# Driver.net
KiCad netlist of a schematic drawn in Altium Designer
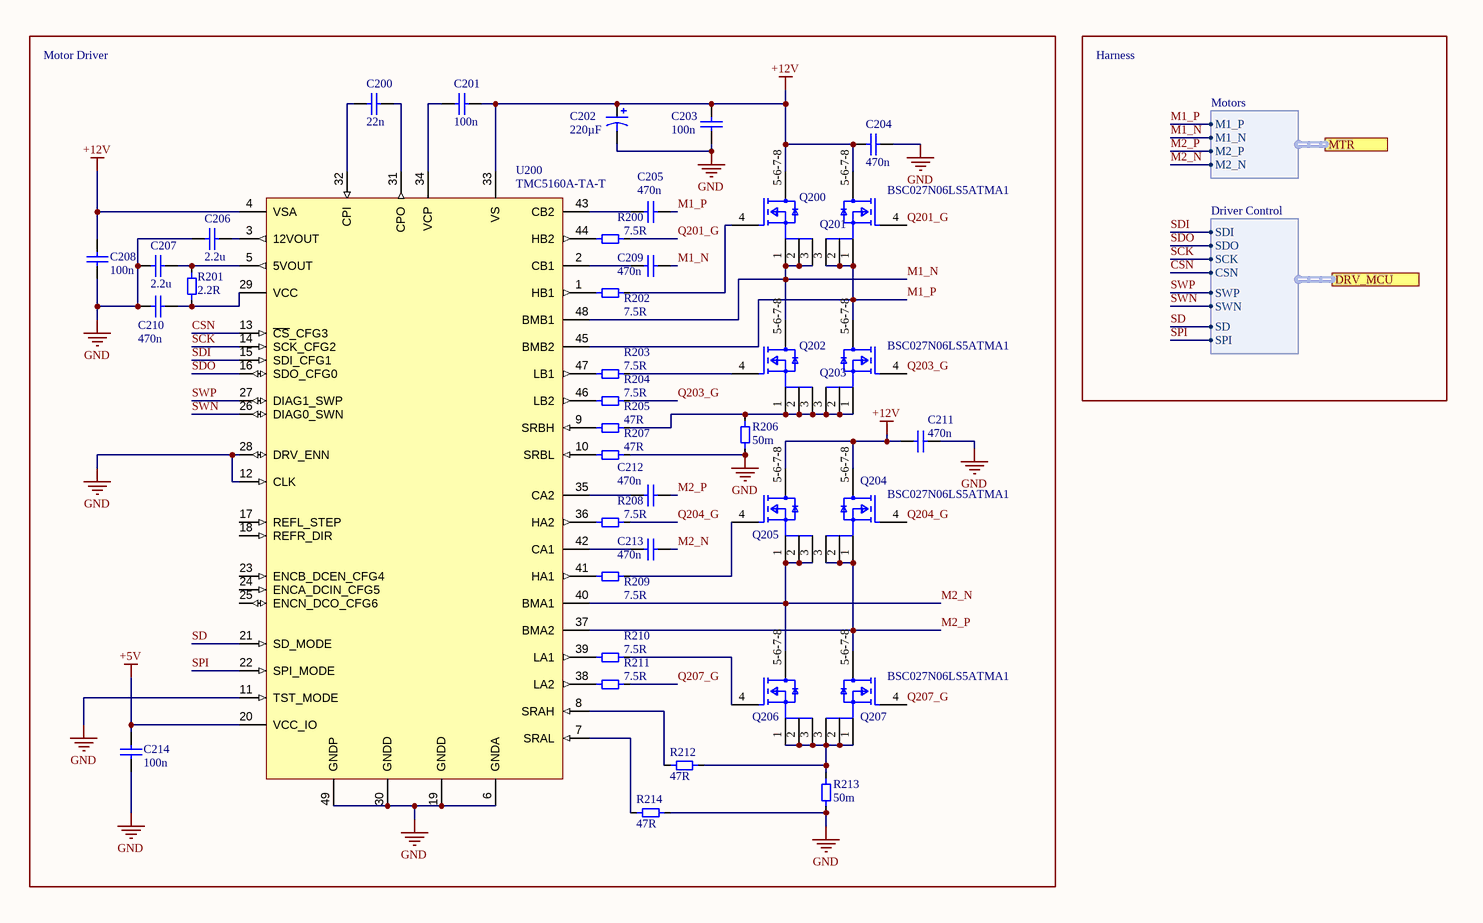
[diagram p0: Driver.SchDoc, right]

(export (version "E")
  (design (tool "Eeschema 10.0.6"))
  (components
    (comp (ref "C200")
      (value "22n")
      (footprint "MLCC_0603_M")
      (description "MLCC, 0603, 22n, 10%, 6.3V, X7R")
      (fields (field (name "MANUFACTURER") "Any") (field (name "TOLERANCE") "10%"))
      (libsource (lib "Krakul Vault") (part "CAPACITOR_NONPOL_IEC"))
    )
    (comp (ref "C201")
      (value "100n")
      (footprint "MLCC_0603_M")
      (description "MLCC, 0603, 100n, 10%, 35V, X7R")
      (fields (field (name "MANUFACTURER") "Any") (field (name "VOLTAGE") "35V"))
      (libsource (lib "Krakul Vault") (part "CAPACITOR_NONPOL_IEC"))
    )
    (comp (ref "C202")
      (value "220µF")
      (footprint "8mm Cap")
      (description "Panasonic EEUFS1H221L - Aluminum Electrolytic Capacitors (Radial Lead Type)")
      (fields (field (name "VOLTAGE") "50V") (field (name "MANUFACTURER") "Any"))
      (libsource (lib "Krakul Vault") (part "GENERIC ELECTROLYTIC CAP"))
    )
    (comp (ref "C203")
      (value "100n")
      (footprint "MLCC_0603_M")
      (description "MLCC, 0603, 100n, 10%, 35V, X7R")
      (fields (field (name "MANUFACTURER") "Any") (field (name "VOLTAGE") "35V"))
      (libsource (lib "Krakul Vault") (part "CAPACITOR_NONPOL_IEC"))
    )
    (comp (ref "C204")
      (value "470n")
      (footprint "MLCC_0805_M")
      (description "MLCC, 0805, 470n, 10%, 6.3V, X7R")
      (fields (field (name "TOLERANCE") "10%") (field (name "VOLTAGE") "6,3V"))
      (libsource (lib "Krakul Vault") (part "CAPACITOR_NONPOL_IEC"))
    )
    (comp (ref "C205")
      (value "470n")
      (footprint "MLCC_0805_M")
      (description "MLCC, 0805, 470n, 10%, 6.3V, X7R")
      (fields (field (name "TOLERANCE") "10%") (field (name "VOLTAGE") "6,3V"))
      (libsource (lib "Krakul Vault") (part "CAPACITOR_NONPOL_IEC"))
    )
    (comp (ref "C206")
      (value "2.2u")
      (footprint "MLCC_0805_M")
      (description "MLCC, 0805, 2.2u, 10%, 6.3V, X7R")
      (fields (field (name "VOLTAGE") "6,3V") (field (name "TOLERANCE") "10%"))
      (libsource (lib "Krakul Vault") (part "CAPACITOR_NONPOL_IEC"))
    )
    (comp (ref "C207")
      (value "2.2u")
      (footprint "MLCC_0805_M")
      (description "MLCC, 0805, 2.2u, 10%, 6.3V, X7R")
      (fields (field (name "VOLTAGE") "6,3V") (field (name "TOLERANCE") "10%"))
      (libsource (lib "Krakul Vault") (part "CAPACITOR_NONPOL_IEC"))
    )
    (comp (ref "C208")
      (value "100n")
      (footprint "MLCC_0603_M")
      (description "MLCC, 0603, 100n, 10%, 35V, X7R")
      (fields (field (name "MANUFACTURER") "Any") (field (name "VOLTAGE") "35V"))
      (libsource (lib "Krakul Vault") (part "CAPACITOR_NONPOL_IEC"))
    )
    (comp (ref "C209")
      (value "470n")
      (footprint "MLCC_0805_M")
      (description "MLCC, 0805, 470n, 10%, 6.3V, X7R")
      (fields (field (name "TOLERANCE") "10%") (field (name "VOLTAGE") "6,3V"))
      (libsource (lib "Krakul Vault") (part "CAPACITOR_NONPOL_IEC"))
    )
    (comp (ref "C210")
      (value "470n")
      (footprint "MLCC_0805_M")
      (description "MLCC, 0805, 470n, 10%, 6.3V, X7R")
      (fields (field (name "TOLERANCE") "10%") (field (name "VOLTAGE") "6,3V"))
      (libsource (lib "Krakul Vault") (part "CAPACITOR_NONPOL_IEC"))
    )
    (comp (ref "C211")
      (value "470n")
      (footprint "MLCC_0805_M")
      (description "MLCC, 0805, 470n, 10%, 6.3V, X7R")
      (fields (field (name "TOLERANCE") "10%") (field (name "VOLTAGE") "6,3V"))
      (libsource (lib "Krakul Vault") (part "CAPACITOR_NONPOL_IEC"))
    )
    (comp (ref "C212")
      (value "470n")
      (footprint "MLCC_0805_M")
      (description "MLCC, 0805, 470n, 10%, 6.3V, X7R")
      (fields (field (name "TOLERANCE") "10%") (field (name "VOLTAGE") "6,3V"))
      (libsource (lib "Krakul Vault") (part "CAPACITOR_NONPOL_IEC"))
    )
    (comp (ref "C213")
      (value "470n")
      (footprint "MLCC_0805_M")
      (description "MLCC, 0805, 470n, 10%, 6.3V, X7R")
      (fields (field (name "TOLERANCE") "10%") (field (name "VOLTAGE") "6,3V"))
      (libsource (lib "Krakul Vault") (part "CAPACITOR_NONPOL_IEC"))
    )
    (comp (ref "C214")
      (value "100n")
      (footprint "MLCC_0603_M")
      (description "MLCC, 0603, 100n, 10%, 35V, X7R")
      (fields (field (name "MANUFACTURER") "Any") (field (name "VOLTAGE") "35V"))
      (libsource (lib "Krakul Vault") (part "CAPACITOR_NONPOL_IEC"))
    )
    (comp (ref "Q200")
      (value "BSC027N06LS5ATMA1")
      (footprint "FP-PG-TDSON-8-MFG")
      (description "Power MOSFET, N Channel, 60 V, 100 A, 0.0027 ohm, TDSON, Surface Mount")
      (fields (field (name "MANUFACTURER") "Infineon Technologies"))
      (libsource (lib "Krakul Vault") (part "d156af113c66deab26b3d7f562d4ecf"))
    )
    (comp (ref "Q201")
      (value "BSC027N06LS5ATMA1")
      (footprint "FP-PG-TDSON-8-MFG")
      (description "Power MOSFET, N Channel, 60 V, 100 A, 0.0027 ohm, TDSON, Surface Mount")
      (fields (field (name "MANUFACTURER") "Infineon Technologies"))
      (libsource (lib "Krakul Vault") (part "d156af113c66deab26b3d7f562d4ecf"))
    )
    (comp (ref "Q202")
      (value "BSC027N06LS5ATMA1")
      (footprint "FP-PG-TDSON-8-MFG")
      (description "Power MOSFET, N Channel, 60 V, 100 A, 0.0027 ohm, TDSON, Surface Mount")
      (fields (field (name "MANUFACTURER") "Infineon Technologies"))
      (libsource (lib "Krakul Vault") (part "d156af113c66deab26b3d7f562d4ecf"))
    )
    (comp (ref "Q203")
      (value "BSC027N06LS5ATMA1")
      (footprint "FP-PG-TDSON-8-MFG")
      (description "Power MOSFET, N Channel, 60 V, 100 A, 0.0027 ohm, TDSON, Surface Mount")
      (fields (field (name "MANUFACTURER") "Infineon Technologies"))
      (libsource (lib "Krakul Vault") (part "d156af113c66deab26b3d7f562d4ecf"))
    )
    (comp (ref "Q204")
      (value "BSC027N06LS5ATMA1")
      (footprint "FP-PG-TDSON-8-MFG")
      (description "Power MOSFET, N Channel, 60 V, 100 A, 0.0027 ohm, TDSON, Surface Mount")
      (fields (field (name "MANUFACTURER") "Infineon Technologies"))
      (libsource (lib "Krakul Vault") (part "d156af113c66deab26b3d7f562d4ecf"))
    )
    (comp (ref "Q205")
      (value "BSC027N06LS5ATMA1")
      (footprint "FP-PG-TDSON-8-MFG")
      (description "Power MOSFET, N Channel, 60 V, 100 A, 0.0027 ohm, TDSON, Surface Mount")
      (fields (field (name "MANUFACTURER") "Infineon Technologies"))
      (libsource (lib "Krakul Vault") (part "d156af113c66deab26b3d7f562d4ecf"))
    )
    (comp (ref "Q206")
      (value "BSC027N06LS5ATMA1")
      (footprint "FP-PG-TDSON-8-MFG")
      (description "Power MOSFET, N Channel, 60 V, 100 A, 0.0027 ohm, TDSON, Surface Mount")
      (fields (field (name "MANUFACTURER") "Infineon Technologies"))
      (libsource (lib "Krakul Vault") (part "d156af113c66deab26b3d7f562d4ecf"))
    )
    (comp (ref "Q207")
      (value "BSC027N06LS5ATMA1")
      (footprint "FP-PG-TDSON-8-MFG")
      (description "Power MOSFET, N Channel, 60 V, 100 A, 0.0027 ohm, TDSON, Surface Mount")
      (fields (field (name "MANUFACTURER") "Infineon Technologies"))
      (libsource (lib "Krakul Vault") (part "d156af113c66deab26b3d7f562d4ecf"))
    )
    (comp (ref "R200")
      (value "7.5R")
      (footprint "Resistor_0603_M")
      (description "Resistor, 0603, 7.5R, 1%, 1/10W")
      (fields (field (name "POWER") "100mW") (field (name "TOLERANCE") "1%"))
      (libsource (lib "Krakul Vault") (part "RESISTOR_GENERIC_IEC"))
    )
    (comp (ref "R201")
      (value "2.2R")
      (footprint "Resistor_0603_M")
      (description "Resistor, 0603, 2.2R, 1%, 1/10W")
      (fields (field (name "MANUFACTURER") "Any") (field (name "POWER") "100mW"))
      (libsource (lib "Krakul Vault") (part "RESISTOR_GENERIC_IEC"))
    )
    (comp (ref "R202")
      (value "7.5R")
      (footprint "Resistor_0603_M")
      (description "Resistor, 0603, 7.5R, 1%, 1/10W")
      (fields (field (name "POWER") "100mW") (field (name "TOLERANCE") "1%"))
      (libsource (lib "Krakul Vault") (part "RESISTOR_GENERIC_IEC"))
    )
    (comp (ref "R203")
      (value "7.5R")
      (footprint "Resistor_0603_M")
      (description "Resistor, 0603, 7.5R, 1%, 1/10W")
      (fields (field (name "POWER") "100mW") (field (name "TOLERANCE") "1%"))
      (libsource (lib "Krakul Vault") (part "RESISTOR_GENERIC_IEC"))
    )
    (comp (ref "R204")
      (value "7.5R")
      (footprint "Resistor_0603_M")
      (description "Resistor, 0603, 7.5R, 1%, 1/10W")
      (fields (field (name "POWER") "100mW") (field (name "TOLERANCE") "1%"))
      (libsource (lib "Krakul Vault") (part "RESISTOR_GENERIC_IEC"))
    )
    (comp (ref "R205")
      (value "47R")
      (footprint "Resistor_0603_M")
      (description "Resistor, 0603, 47R, 1%, 1/10W")
      (fields (field (name "TOLERANCE") "1%") (field (name "MANUFACTURER") "Any"))
      (libsource (lib "Krakul Vault") (part "RESISTOR_GENERIC_IEC"))
    )
    (comp (ref "R206")
      (value "50m")
      (footprint "PE0612FKM7W0R05L-Footprint-1")
      (description "Current Sensor-Low TCR Chip Resistor Wide Terminal Metal Alloy 0612 50mOhm 1% Emboss T/R")
      (fields (field (name "MANUFACTURER") "Any") (field (name "PART NUMBER") "PE0612FKM7W0R05L"))
      (libsource (lib "Krakul Vault") (part "RESISTOR_WITH_SENSE"))
    )
    (comp (ref "R207")
      (value "47R")
      (footprint "Resistor_0603_M")
      (description "Resistor, 0603, 47R, 1%, 1/10W")
      (fields (field (name "TOLERANCE") "1%") (field (name "MANUFACTURER") "Any"))
      (libsource (lib "Krakul Vault") (part "RESISTOR_GENERIC_IEC"))
    )
    (comp (ref "R208")
      (value "7.5R")
      (footprint "Resistor_0603_M")
      (description "Resistor, 0603, 7.5R, 1%, 1/10W")
      (fields (field (name "POWER") "100mW") (field (name "TOLERANCE") "1%"))
      (libsource (lib "Krakul Vault") (part "RESISTOR_GENERIC_IEC"))
    )
    (comp (ref "R209")
      (value "7.5R")
      (footprint "Resistor_0603_M")
      (description "Resistor, 0603, 7.5R, 1%, 1/10W")
      (fields (field (name "POWER") "100mW") (field (name "TOLERANCE") "1%"))
      (libsource (lib "Krakul Vault") (part "RESISTOR_GENERIC_IEC"))
    )
    (comp (ref "R210")
      (value "7.5R")
      (footprint "Resistor_0603_M")
      (description "Resistor, 0603, 7.5R, 1%, 1/10W")
      (fields (field (name "POWER") "100mW") (field (name "TOLERANCE") "1%"))
      (libsource (lib "Krakul Vault") (part "RESISTOR_GENERIC_IEC"))
    )
    (comp (ref "R211")
      (value "7.5R")
      (footprint "Resistor_0603_M")
      (description "Resistor, 0603, 7.5R, 1%, 1/10W")
      (fields (field (name "POWER") "100mW") (field (name "TOLERANCE") "1%"))
      (libsource (lib "Krakul Vault") (part "RESISTOR_GENERIC_IEC"))
    )
    (comp (ref "R212")
      (value "47R")
      (footprint "Resistor_0603_M")
      (description "Resistor, 0603, 47R, 1%, 1/10W")
      (fields (field (name "TOLERANCE") "1%") (field (name "MANUFACTURER") "Any"))
      (libsource (lib "Krakul Vault") (part "RESISTOR_GENERIC_IEC"))
    )
    (comp (ref "R213")
      (value "50m")
      (footprint "PE0612FKM7W0R05L-Footprint-1")
      (description "Current Sensor-Low TCR Chip Resistor Wide Terminal Metal Alloy 0612 50mOhm 1% Emboss T/R")
      (fields (field (name "MANUFACTURER") "Any") (field (name "PART NUMBER") "PE0612FKM7W0R05L"))
      (libsource (lib "Krakul Vault") (part "RESISTOR_WITH_SENSE"))
    )
    (comp (ref "R214")
      (value "47R")
      (footprint "Resistor_0603_M")
      (description "Resistor, 0603, 47R, 1%, 1/10W")
      (fields (field (name "TOLERANCE") "1%") (field (name "MANUFACTURER") "Any"))
      (libsource (lib "Krakul Vault") (part "RESISTOR_GENERIC_IEC"))
    )
    (comp (ref "U200")
      (value "TMC5160A-TA-T")
      (footprint "TQFP80P900X900X120-32N")
      (description "IC Mtr Drvr Bipolar 8-60V 48TQFP")
      (fields (field (name "MANUFACTURER") "Trinamic Motion Control GmbH"))
      (libsource (lib "Krakul Vault") (part "TMC5160A-TA"))
    )
  )
  (nets
    (net (code "4") (name "+5V") (class "Default")
      (node (ref "C214") (pin "2") (pinfunction "2_2") (pintype "passive"))
      (node (ref "U200") (pin "20") (pinfunction "VCC_IO_20") (pintype "power_in"))
    )
    (net (code "5") (name "+12V") (class "Default")
      (node (ref "C201") (pin "1") (pinfunction "1_1") (pintype "passive"))
      (node (ref "C202") (pin "2") (pinfunction "2_2") (pintype "passive"))
      (node (ref "C203") (pin "2") (pinfunction "2_2") (pintype "passive"))
      (node (ref "C204") (pin "2") (pinfunction "2_2") (pintype "passive"))
      (node (ref "C208") (pin "2") (pinfunction "2_2") (pintype "passive"))
      (node (ref "C211") (pin "1") (pinfunction "1_1") (pintype "passive"))
      (node (ref "Q200") (pin "5-6-7-8") (pinfunction "D_5-6-7-8") (pintype "passive"))
      (node (ref "Q201") (pin "5-6-7-8") (pinfunction "D_5-6-7-8") (pintype "passive"))
      (node (ref "Q204") (pin "5-6-7-8") (pinfunction "D_5-6-7-8") (pintype "passive"))
      (node (ref "Q205") (pin "5-6-7-8") (pinfunction "D_5-6-7-8") (pintype "passive"))
      (node (ref "U200") (pin "33") (pinfunction "VS_33") (pintype "power_in"))
      (node (ref "U200") (pin "4") (pinfunction "VSA_4") (pintype "power_in"))
    )
    (net (code "6") (name "/CSN") (class "Default")
      (node (ref "U200") (pin "13") (pinfunction "~{CS}_CFG3_13") (pintype "input"))
    )
    (net (code "7") (name "/M1_N") (class "Default")
      (node (ref "C209") (pin "2") (pinfunction "2_2") (pintype "passive"))
      (node (ref "Q200") (pin "1") (pinfunction "S_1") (pintype "passive"))
      (node (ref "Q200") (pin "2") (pinfunction "S_2") (pintype "passive"))
      (node (ref "Q200") (pin "3") (pinfunction "S_3") (pintype "passive"))
      (node (ref "Q202") (pin "5-6-7-8") (pinfunction "D_5-6-7-8") (pintype "passive"))
      (node (ref "U200") (pin "48") (pinfunction "BMB1_48") (pintype "passive"))
    )
    (net (code "8") (name "/M1_P") (class "Default")
      (node (ref "C205") (pin "2") (pinfunction "2_2") (pintype "passive"))
      (node (ref "Q201") (pin "1") (pinfunction "S_1") (pintype "passive"))
      (node (ref "Q201") (pin "2") (pinfunction "S_2") (pintype "passive"))
      (node (ref "Q201") (pin "3") (pinfunction "S_3") (pintype "passive"))
      (node (ref "Q203") (pin "5-6-7-8") (pinfunction "D_5-6-7-8") (pintype "passive"))
      (node (ref "U200") (pin "45") (pinfunction "BMB2_45") (pintype "passive"))
    )
    (net (code "9") (name "/M2_N") (class "Default")
      (node (ref "C213") (pin "2") (pinfunction "2_2") (pintype "passive"))
      (node (ref "Q205") (pin "1") (pinfunction "S_1") (pintype "passive"))
      (node (ref "Q205") (pin "2") (pinfunction "S_2") (pintype "passive"))
      (node (ref "Q205") (pin "3") (pinfunction "S_3") (pintype "passive"))
      (node (ref "Q206") (pin "5-6-7-8") (pinfunction "D_5-6-7-8") (pintype "passive"))
      (node (ref "U200") (pin "40") (pinfunction "BMA1_40") (pintype "passive"))
    )
    (net (code "10") (name "/M2_P") (class "Default")
      (node (ref "C212") (pin "2") (pinfunction "2_2") (pintype "passive"))
      (node (ref "Q204") (pin "1") (pinfunction "S_1") (pintype "passive"))
      (node (ref "Q204") (pin "2") (pinfunction "S_2") (pintype "passive"))
      (node (ref "Q204") (pin "3") (pinfunction "S_3") (pintype "passive"))
      (node (ref "Q207") (pin "5-6-7-8") (pinfunction "D_5-6-7-8") (pintype "passive"))
      (node (ref "U200") (pin "37") (pinfunction "BMA2_37") (pintype "passive"))
    )
    (net (code "11") (name "/Q201_G") (class "Default")
      (node (ref "Q201") (pin "4") (pinfunction "G_4") (pintype "passive"))
      (node (ref "R200") (pin "2") (pinfunction "2_2") (pintype "passive"))
    )
    (net (code "12") (name "/Q203_G") (class "Default")
      (node (ref "Q203") (pin "4") (pinfunction "G_4") (pintype "passive"))
      (node (ref "R204") (pin "2") (pinfunction "2_2") (pintype "passive"))
    )
    (net (code "13") (name "/Q204_G") (class "Default")
      (node (ref "Q204") (pin "4") (pinfunction "G_4") (pintype "passive"))
      (node (ref "R208") (pin "2") (pinfunction "2_2") (pintype "passive"))
    )
    (net (code "14") (name "/Q207_G") (class "Default")
      (node (ref "Q207") (pin "4") (pinfunction "G_4") (pintype "passive"))
      (node (ref "R211") (pin "2") (pinfunction "2_2") (pintype "passive"))
    )
    (net (code "15") (name "/SCK") (class "Default")
      (node (ref "U200") (pin "14") (pinfunction "SCK_CFG2_14") (pintype "input"))
    )
    (net (code "16") (name "/SD") (class "Default")
      (node (ref "U200") (pin "21") (pinfunction "SD_MODE_21") (pintype "input"))
    )
    (net (code "17") (name "/SDI") (class "Default")
      (node (ref "U200") (pin "15") (pinfunction "SDI_CFG1_15") (pintype "input"))
    )
    (net (code "18") (name "/SDO") (class "Default")
      (node (ref "U200") (pin "16") (pinfunction "SDO_CFG0_16") (pintype "bidirectional"))
    )
    (net (code "19") (name "/SPI") (class "Default")
      (node (ref "U200") (pin "22") (pinfunction "SPI_MODE_22") (pintype "input"))
    )
    (net (code "20") (name "/SWN") (class "Default")
      (node (ref "U200") (pin "26") (pinfunction "DIAG0_SWN_26") (pintype "bidirectional"))
    )
    (net (code "21") (name "/SWP") (class "Default")
      (node (ref "U200") (pin "27") (pinfunction "DIAG1_SWP_27") (pintype "bidirectional"))
    )
    (net (code "24") (name "GND") (class "Default")
      (node (ref "C202") (pin "1") (pinfunction "1_1") (pintype "passive"))
      (node (ref "C203") (pin "1") (pinfunction "1_1") (pintype "passive"))
      (node (ref "C204") (pin "1") (pinfunction "1_1") (pintype "passive"))
      (node (ref "C206") (pin "1") (pinfunction "1_1") (pintype "passive"))
      (node (ref "C207") (pin "1") (pinfunction "1_1") (pintype "passive"))
      (node (ref "C208") (pin "1") (pinfunction "1_1") (pintype "passive"))
      (node (ref "C210") (pin "1") (pinfunction "1_1") (pintype "passive"))
      (node (ref "C211") (pin "2") (pinfunction "2_2") (pintype "passive"))
      (node (ref "C214") (pin "1") (pinfunction "1_1") (pintype "passive"))
      (node (ref "R206") (pin "1") (pinfunction "1_1") (pintype "passive"))
      (node (ref "R207") (pin "1") (pinfunction "1_1") (pintype "passive"))
      (node (ref "R213") (pin "1") (pinfunction "1_1") (pintype "passive"))
      (node (ref "R214") (pin "1") (pinfunction "1_1") (pintype "passive"))
      (node (ref "U200") (pin "11") (pinfunction "TST_MODE_11") (pintype "input"))
      (node (ref "U200") (pin "12") (pinfunction "CLK_12") (pintype "input"))
      (node (ref "U200") (pin "19") (pinfunction "GNDD_19") (pintype "power_in"))
      (node (ref "U200") (pin "28") (pinfunction "DRV_ENN_28") (pintype "bidirectional"))
      (node (ref "U200") (pin "30") (pinfunction "GNDD_30") (pintype "power_in"))
      (node (ref "U200") (pin "49") (pinfunction "GNDP_49") (pintype "power_in"))
      (node (ref "U200") (pin "6") (pinfunction "GNDA_6") (pintype "power_in"))
    )
    (net (code "25") (name "Net-(Q200-G)") (class "Default")
      (node (ref "Q200") (pin "4") (pinfunction "G_4") (pintype "passive"))
      (node (ref "R202") (pin "2") (pinfunction "2_2") (pintype "passive"))
    )
    (net (code "26") (name "Net-(Q202-G)") (class "Default")
      (node (ref "Q202") (pin "4") (pinfunction "G_4") (pintype "passive"))
      (node (ref "R203") (pin "2") (pinfunction "2_2") (pintype "passive"))
    )
    (net (code "27") (name "Net-(Q202-S-Pad1)") (class "Default")
      (node (ref "Q202") (pin "1") (pinfunction "S_1") (pintype "passive"))
      (node (ref "Q202") (pin "2") (pinfunction "S_2") (pintype "passive"))
      (node (ref "Q202") (pin "3") (pinfunction "S_3") (pintype "passive"))
      (node (ref "Q203") (pin "1") (pinfunction "S_1") (pintype "passive"))
      (node (ref "Q203") (pin "2") (pinfunction "S_2") (pintype "passive"))
      (node (ref "Q203") (pin "3") (pinfunction "S_3") (pintype "passive"))
      (node (ref "R205") (pin "1") (pinfunction "1_1") (pintype "passive"))
      (node (ref "R206") (pin "2") (pinfunction "1_2") (pintype "passive"))
    )
    (net (code "28") (name "Net-(Q205-G)") (class "Default")
      (node (ref "Q205") (pin "4") (pinfunction "G_4") (pintype "passive"))
      (node (ref "R209") (pin "2") (pinfunction "2_2") (pintype "passive"))
    )
    (net (code "29") (name "Net-(Q206-G)") (class "Default")
      (node (ref "Q206") (pin "4") (pinfunction "G_4") (pintype "passive"))
      (node (ref "R210") (pin "2") (pinfunction "2_2") (pintype "passive"))
    )
    (net (code "30") (name "Net-(Q206-S-Pad1)") (class "Default")
      (node (ref "Q206") (pin "1") (pinfunction "S_1") (pintype "passive"))
      (node (ref "Q206") (pin "2") (pinfunction "S_2") (pintype "passive"))
      (node (ref "Q206") (pin "3") (pinfunction "S_3") (pintype "passive"))
      (node (ref "Q207") (pin "1") (pinfunction "S_1") (pintype "passive"))
      (node (ref "Q207") (pin "2") (pinfunction "S_2") (pintype "passive"))
      (node (ref "Q207") (pin "3") (pinfunction "S_3") (pintype "passive"))
      (node (ref "R212") (pin "1") (pinfunction "1_1") (pintype "passive"))
      (node (ref "R213") (pin "2") (pinfunction "1_2") (pintype "passive"))
    )
    (net (code "31") (name "Net-(U200-5VOUT)") (class "Default")
      (node (ref "C207") (pin "2") (pinfunction "2_2") (pintype "passive"))
      (node (ref "R201") (pin "2") (pinfunction "2_2") (pintype "passive"))
      (node (ref "U200") (pin "5") (pinfunction "5VOUT_5") (pintype "output"))
    )
    (net (code "32") (name "Net-(U200-12VOUT)") (class "Default")
      (node (ref "C206") (pin "2") (pinfunction "2_2") (pintype "passive"))
      (node (ref "U200") (pin "3") (pinfunction "12VOUT_3") (pintype "output"))
    )
    (net (code "33") (name "Net-(U200-CA1)") (class "Default")
      (node (ref "C213") (pin "1") (pinfunction "1_1") (pintype "passive"))
      (node (ref "U200") (pin "42") (pinfunction "CA1_42") (pintype "passive"))
    )
    (net (code "34") (name "Net-(U200-CA2)") (class "Default")
      (node (ref "C212") (pin "1") (pinfunction "1_1") (pintype "passive"))
      (node (ref "U200") (pin "35") (pinfunction "CA2_35") (pintype "passive"))
    )
    (net (code "35") (name "Net-(U200-CB1)") (class "Default")
      (node (ref "C209") (pin "1") (pinfunction "1_1") (pintype "passive"))
      (node (ref "U200") (pin "2") (pinfunction "CB1_2") (pintype "passive"))
    )
    (net (code "36") (name "Net-(U200-CB2)") (class "Default")
      (node (ref "C205") (pin "1") (pinfunction "1_1") (pintype "passive"))
      (node (ref "U200") (pin "43") (pinfunction "CB2_43") (pintype "passive"))
    )
    (net (code "37") (name "Net-(U200-CPI)") (class "Default")
      (node (ref "C200") (pin "1") (pinfunction "1_1") (pintype "passive"))
      (node (ref "U200") (pin "32") (pinfunction "CPI_32") (pintype "input"))
    )
    (net (code "38") (name "Net-(U200-CPO)") (class "Default")
      (node (ref "C200") (pin "2") (pinfunction "2_2") (pintype "passive"))
      (node (ref "U200") (pin "31") (pinfunction "CPO_31") (pintype "output"))
    )
    (net (code "39") (name "Net-(U200-HA1)") (class "Default")
      (node (ref "R209") (pin "1") (pinfunction "1_1") (pintype "passive"))
      (node (ref "U200") (pin "41") (pinfunction "HA1_41") (pintype "output"))
    )
    (net (code "40") (name "Net-(U200-HA2)") (class "Default")
      (node (ref "R208") (pin "1") (pinfunction "1_1") (pintype "passive"))
      (node (ref "U200") (pin "36") (pinfunction "HA2_36") (pintype "output"))
    )
    (net (code "41") (name "Net-(U200-HB1)") (class "Default")
      (node (ref "R202") (pin "1") (pinfunction "1_1") (pintype "passive"))
      (node (ref "U200") (pin "1") (pinfunction "HB1_1") (pintype "output"))
    )
    (net (code "42") (name "Net-(U200-HB2)") (class "Default")
      (node (ref "R200") (pin "1") (pinfunction "1_1") (pintype "passive"))
      (node (ref "U200") (pin "44") (pinfunction "HB2_44") (pintype "output"))
    )
    (net (code "43") (name "Net-(U200-LA1)") (class "Default")
      (node (ref "R210") (pin "1") (pinfunction "1_1") (pintype "passive"))
      (node (ref "U200") (pin "39") (pinfunction "LA1_39") (pintype "output"))
    )
    (net (code "44") (name "Net-(U200-LA2)") (class "Default")
      (node (ref "R211") (pin "1") (pinfunction "1_1") (pintype "passive"))
      (node (ref "U200") (pin "38") (pinfunction "LA2_38") (pintype "output"))
    )
    (net (code "45") (name "Net-(U200-LB1)") (class "Default")
      (node (ref "R203") (pin "1") (pinfunction "1_1") (pintype "passive"))
      (node (ref "U200") (pin "47") (pinfunction "LB1_47") (pintype "output"))
    )
    (net (code "46") (name "Net-(U200-LB2)") (class "Default")
      (node (ref "R204") (pin "1") (pinfunction "1_1") (pintype "passive"))
      (node (ref "U200") (pin "46") (pinfunction "LB2_46") (pintype "output"))
    )
    (net (code "47") (name "Net-(U200-SRAH)") (class "Default")
      (node (ref "R212") (pin "2") (pinfunction "2_2") (pintype "passive"))
      (node (ref "U200") (pin "8") (pinfunction "SRAH_8") (pintype "input"))
    )
    (net (code "48") (name "Net-(U200-SRAL)") (class "Default")
      (node (ref "R214") (pin "2") (pinfunction "2_2") (pintype "passive"))
      (node (ref "U200") (pin "7") (pinfunction "SRAL_7") (pintype "input"))
    )
    (net (code "49") (name "Net-(U200-SRBH)") (class "Default")
      (node (ref "R205") (pin "2") (pinfunction "2_2") (pintype "passive"))
      (node (ref "U200") (pin "9") (pinfunction "SRBH_9") (pintype "input"))
    )
    (net (code "50") (name "Net-(U200-SRBL)") (class "Default")
      (node (ref "R207") (pin "2") (pinfunction "2_2") (pintype "passive"))
      (node (ref "U200") (pin "10") (pinfunction "SRBL_10") (pintype "input"))
    )
    (net (code "51") (name "Net-(U200-VCC)") (class "Default")
      (node (ref "C210") (pin "2") (pinfunction "2_2") (pintype "passive"))
      (node (ref "R201") (pin "1") (pinfunction "1_1") (pintype "passive"))
      (node (ref "U200") (pin "29") (pinfunction "VCC_29") (pintype "power_in"))
    )
    (net (code "52") (name "Net-(U200-VCP)") (class "Default")
      (node (ref "C201") (pin "2") (pinfunction "2_2") (pintype "passive"))
      (node (ref "U200") (pin "34") (pinfunction "VCP_34") (pintype "power_in"))
    )
    (net (code "53") (name "unconnected-(U200-ENCA_DCIN_CFG5-Pad24)") (class "Default")
      (node (ref "U200") (pin "24") (pinfunction "ENCA_DCIN_CFG5_24") (pintype "input"))
    )
    (net (code "54") (name "unconnected-(U200-ENCB_DCEN_CFG4-Pad23)") (class "Default")
      (node (ref "U200") (pin "23") (pinfunction "ENCB_DCEN_CFG4_23") (pintype "input"))
    )
    (net (code "55") (name "unconnected-(U200-ENCN_DCO_CFG6-Pad25)") (class "Default")
      (node (ref "U200") (pin "25") (pinfunction "ENCN_DCO_CFG6_25") (pintype "bidirectional"))
    )
    (net (code "56") (name "unconnected-(U200-REFL_STEP-Pad17)") (class "Default")
      (node (ref "U200") (pin "17") (pinfunction "REFL_STEP_17") (pintype "input"))
    )
    (net (code "57") (name "unconnected-(U200-REFR_DIR-Pad18)") (class "Default")
      (node (ref "U200") (pin "18") (pinfunction "REFR_DIR_18") (pintype "input"))
    )
  )
)
